# I2C-EEPROM.net
KiCad netlist of a schematic drawn in Altium Designer
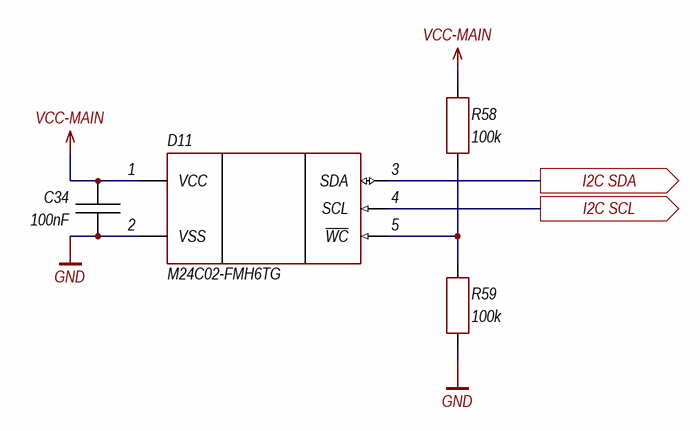
[diagram p0: I2C-EEPROM.SchDoc]

(export (version "E")
  (design (tool "Eeschema 10.0.6"))
  (components
    (comp (ref "C34") (value "100nF") (footprint "CH0402C") (libsource (lib "Discrete") (part "Capacitor")))
    (comp (ref "D11")
      (value "M24C02-FMH6TG")
      (footprint "5-UFDFPN")
      (description "EEPROM, I2C")
      (fields (field (name "MANUFACTURER") "STMicroelectronics"))
      (libsource (lib "Digital") (part "M24C0x-FMH6TG"))
    )
    (comp (ref "R58") (value "100k") (footprint "CH0402R") (libsource (lib "Discrete") (part "Resistor")))
    (comp (ref "R59") (value "100k") (footprint "CH0402R") (libsource (lib "Discrete") (part "Resistor")))
  )
  (nets
    (net (code "1") (name "/I2C SCL") (class "Default")
      (node (ref "D11") (pin "4") (pinfunction "SCL_4") (pintype "input"))
    )
    (net (code "2") (name "/I2C SDA") (class "Default")
      (node (ref "D11") (pin "3") (pinfunction "SDA_3") (pintype "bidirectional"))
    )
    (net (code "3") (name "GND") (class "Default")
      (node (ref "C34") (pin "1") (pinfunction "1_1") (pintype "passive"))
      (node (ref "D11") (pin "2") (pinfunction "VSS_2") (pintype "power_in"))
      (node (ref "R59") (pin "1") (pinfunction "1_1") (pintype "passive"))
    )
    (net (code "4") (name "Net-(D11-~{WC})") (class "Default")
      (node (ref "D11") (pin "5") (pinfunction "~{WC}_5") (pintype "input"))
      (node (ref "R58") (pin "1") (pinfunction "1_1") (pintype "passive"))
      (node (ref "R59") (pin "2") (pinfunction "2_2") (pintype "passive"))
    )
    (net (code "5") (name "VCC-MAIN") (class "Default")
      (node (ref "C34") (pin "2") (pinfunction "2_2") (pintype "passive"))
      (node (ref "D11") (pin "1") (pinfunction "VCC_1") (pintype "power_in"))
      (node (ref "R58") (pin "2") (pinfunction "2_2") (pintype "passive"))
    )
  )
)
